# SCH_WINGLET_ADSB.net
KiCad netlist of a schematic drawn in Altium Designer
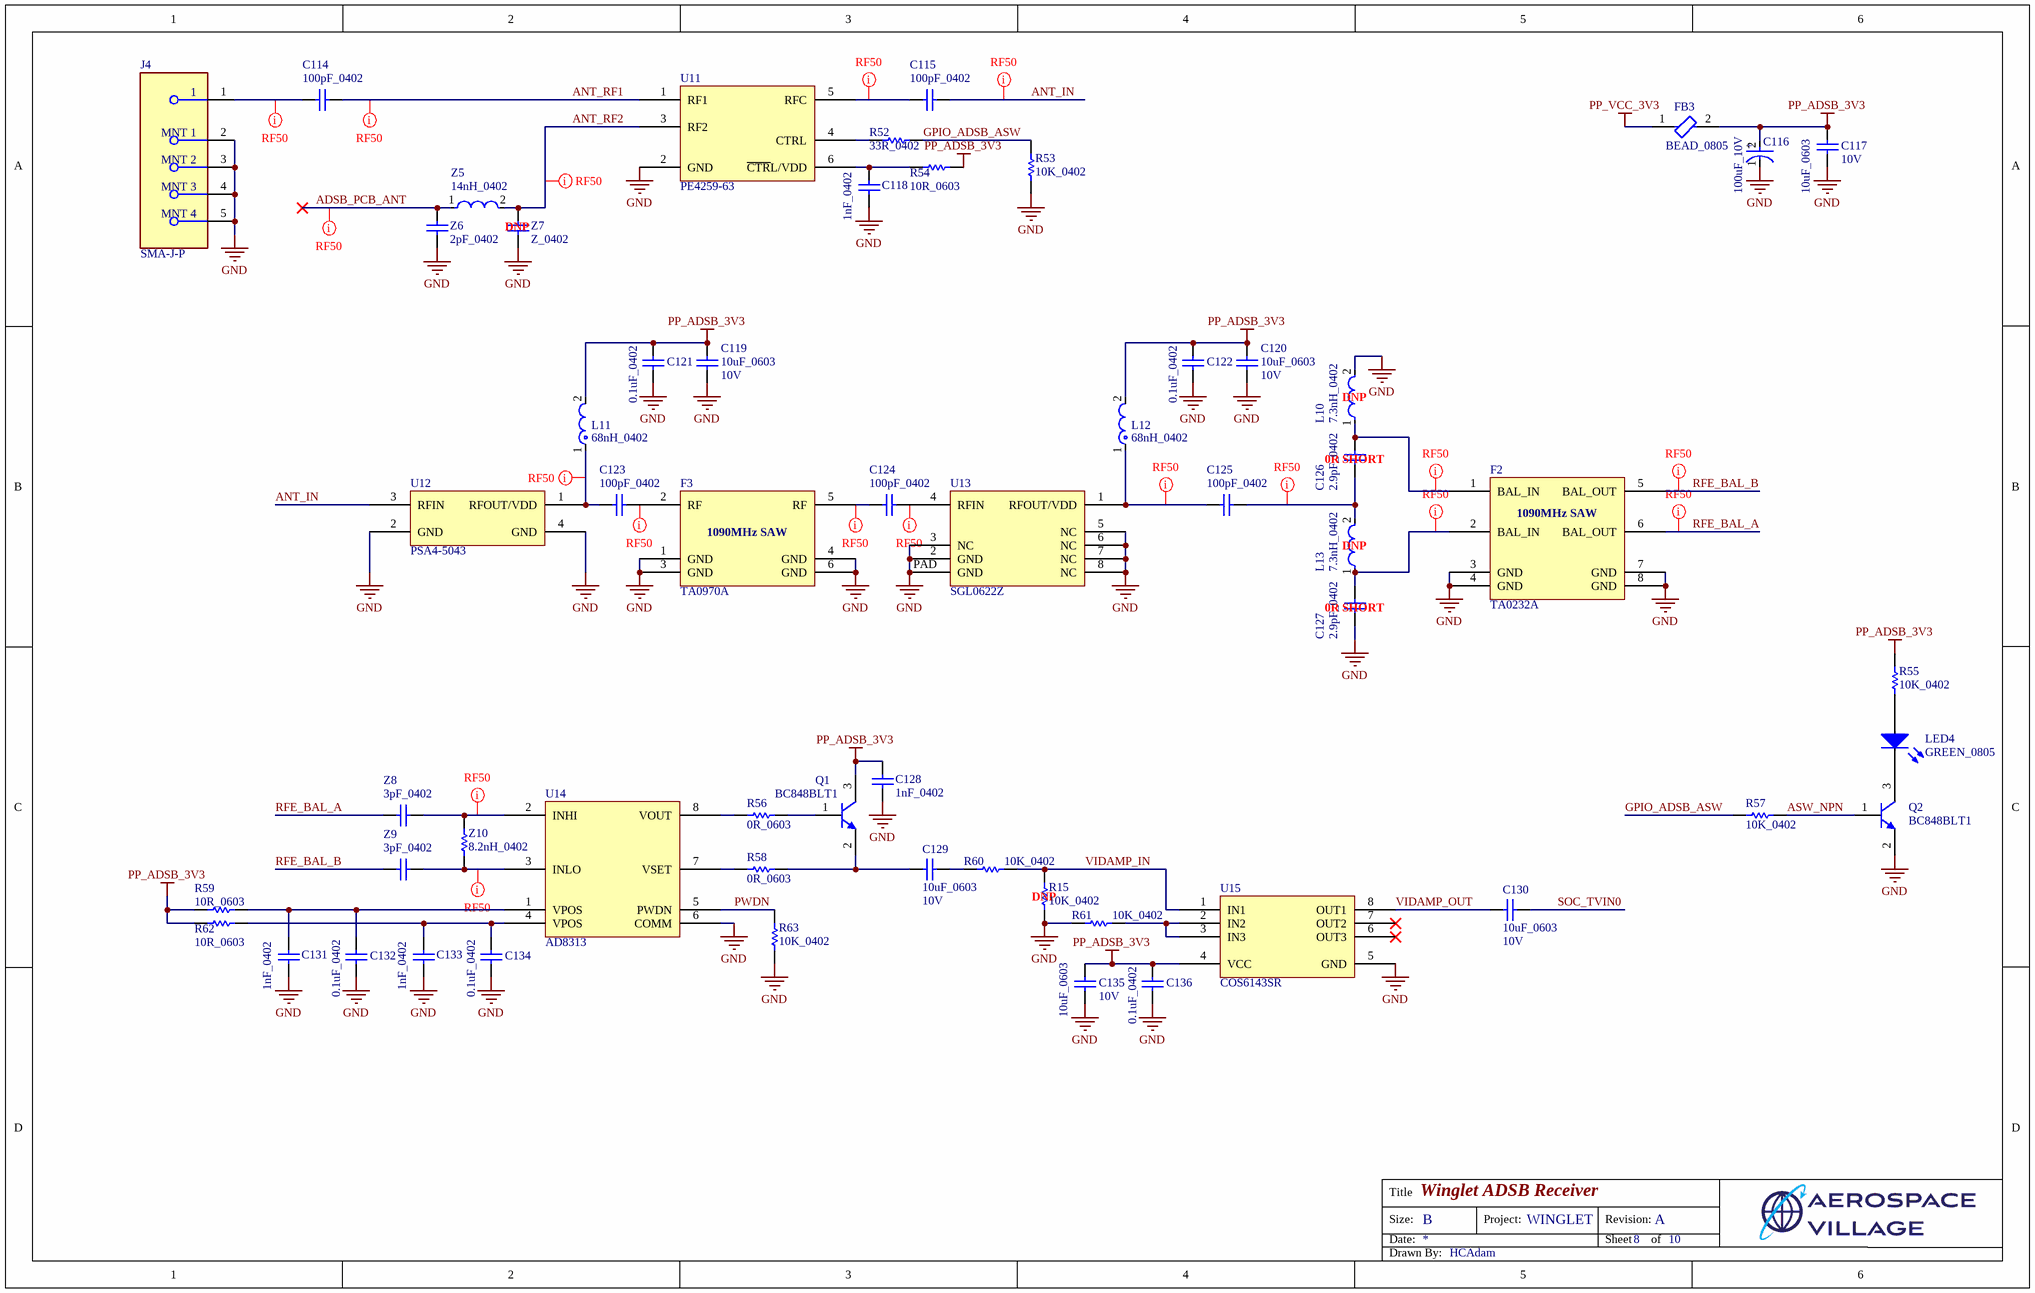
[diagram p0: SCH_WINGLET_ADSB.SchDoc]

(export (version "E")
  (design (tool "Eeschema 10.0.6"))
  (components
    (comp (ref "C114")
      (value "100pF_0402")
      (footprint "CAPC1005X55X25NL05T10")
      (description "GRM1555C1H101JA01D")
      (fields (field (name "MANUFACTURER") "Murata"))
      (libsource (lib "Altium Content Vault") (part "CAP"))
    )
    (comp (ref "C115")
      (value "100pF_0402")
      (footprint "CAPC1005X55X25NL05T10")
      (description "GRM1555C1H101JA01D")
      (fields (field (name "MANUFACTURER") "Murata"))
      (libsource (lib "Altium Content Vault") (part "CAP"))
    )
    (comp (ref "C116")
      (value "100uF_10V")
      (footprint "FP-TAJB-MFG")
      (description "100uF 10V ±10% 1.7Ω SMD CASE-B (3528) Tantalum Capacitor")
      (fields (field (name "VOLTAGE") "6.3V") (field (name "TOLERANCE") "10%"))
      (libsource (lib "Altium Content Vault") (part "203bc49f2ac43e59fd269a8c329ed05"))
    )
    (comp (ref "C117")
      (value "10uF_0603")
      (footprint "CAPC1609X100X15NL20")
      (fields
        (field (name "PART NUMBER") "TACL106M006XTA")
        (field (name "MANUFACTURER") "AVX Interconnect / Elco")
        (field (name "VOLTAGE RATING") "10V")
      )
      (libsource (lib "Altium Content Vault") (part "CAP"))
    )
    (comp (ref "C118")
      (value "1nF_0402")
      (footprint "CAPC1005X56X25NL10T15")
      (description "04025C102KAT4A")
      (fields (field (name "MANUFACTURER") "AVX Interconnect / Elco"))
      (libsource (lib "Altium Content Vault") (part "CAP"))
    )
    (comp (ref "C119")
      (value "10uF_0603")
      (footprint "CAPC1609X100X15NL20")
      (fields
        (field (name "PART NUMBER") "TACL106M006XTA")
        (field (name "MANUFACTURER") "AVX Interconnect / Elco")
        (field (name "VOLTAGE RATING") "10V")
      )
      (libsource (lib "Altium Content Vault") (part "CAP"))
    )
    (comp (ref "C120")
      (value "10uF_0603")
      (footprint "CAPC1609X100X15NL20")
      (fields
        (field (name "PART NUMBER") "TACL106M006XTA")
        (field (name "MANUFACTURER") "AVX Interconnect / Elco")
        (field (name "VOLTAGE RATING") "10V")
      )
      (libsource (lib "Altium Content Vault") (part "CAP"))
    )
    (comp (ref "C121")
      (value "0.1uF_0402")
      (footprint "CAPC1005X56X25NL10T15")
      (description "04026D104KAT2A")
      (fields (field (name "MANUFACTURER") "AVX Interconnect / Elco"))
      (libsource (lib "Altium Content Vault") (part "CAP"))
    )
    (comp (ref "C122")
      (value "0.1uF_0402")
      (footprint "CAPC1005X56X25NL10T15")
      (description "04026D104KAT2A")
      (fields (field (name "MANUFACTURER") "AVX Interconnect / Elco"))
      (libsource (lib "Altium Content Vault") (part "CAP"))
    )
    (comp (ref "C123")
      (value "100pF_0402")
      (footprint "CAPC1005X55X25NL05T10")
      (description "GRM1555C1H101JA01D")
      (fields (field (name "MANUFACTURER") "Murata"))
      (libsource (lib "Altium Content Vault") (part "CAP"))
    )
    (comp (ref "C124")
      (value "100pF_0402")
      (footprint "CAPC1005X55X25NL05T10")
      (description "GRM1555C1H101JA01D")
      (fields (field (name "MANUFACTURER") "Murata"))
      (libsource (lib "Altium Content Vault") (part "CAP"))
    )
    (comp (ref "C125")
      (value "100pF_0402")
      (footprint "CAPC1005X55X25NL05T10")
      (description "GRM1555C1H101JA01D")
      (fields (field (name "MANUFACTURER") "Murata"))
      (libsource (lib "Altium Content Vault") (part "CAP"))
    )
    (comp (ref "C126")
      (value "2.9pF_0402")
      (footprint "CAPC1006X50X20NL10T10")
      (description "04023J2R9BBSTR")
      (fields (field (name "MANUFACTURER") "AVX Interconnect / Elco") (field (name "0R SHORT") "0R SHORT"))
      (libsource (lib "Altium Content Vault") (part "CAP"))
    )
    (comp (ref "C127")
      (value "2.9pF_0402")
      (footprint "CAPC1006X50X20NL10T10")
      (description "04023J2R9BBSTR")
      (fields (field (name "MANUFACTURER") "AVX Interconnect / Elco") (field (name "0R SHORT") "0R SHORT"))
      (libsource (lib "Altium Content Vault") (part "CAP"))
    )
    (comp (ref "C128")
      (value "1nF_0402")
      (footprint "CAPC1005X56X25NL10T15")
      (description "04025C102KAT4A")
      (fields (field (name "MANUFACTURER") "AVX Interconnect / Elco"))
      (libsource (lib "Altium Content Vault") (part "CAP"))
    )
    (comp (ref "C129")
      (value "10uF_0603")
      (footprint "CAPC1609X100X15NL20")
      (fields
        (field (name "PART NUMBER") "TACL106M006XTA")
        (field (name "MANUFACTURER") "AVX Interconnect / Elco")
        (field (name "VOLTAGE RATING") "10V")
      )
      (libsource (lib "Altium Content Vault") (part "CAP"))
    )
    (comp (ref "C130")
      (value "10uF_0603")
      (footprint "CAPC1609X100X15NL20")
      (fields
        (field (name "PART NUMBER") "TACL106M006XTA")
        (field (name "MANUFACTURER") "AVX Interconnect / Elco")
        (field (name "VOLTAGE RATING") "10V")
      )
      (libsource (lib "Altium Content Vault") (part "CAP"))
    )
    (comp (ref "C131")
      (value "1nF_0402")
      (footprint "CAPC1005X56X25NL10T15")
      (description "04025C102KAT4A")
      (fields (field (name "MANUFACTURER") "AVX Interconnect / Elco"))
      (libsource (lib "Altium Content Vault") (part "CAP"))
    )
    (comp (ref "C132")
      (value "0.1uF_0402")
      (footprint "CAPC1005X56X25NL10T15")
      (description "04026D104KAT2A")
      (fields (field (name "MANUFACTURER") "AVX Interconnect / Elco"))
      (libsource (lib "Altium Content Vault") (part "CAP"))
    )
    (comp (ref "C133")
      (value "1nF_0402")
      (footprint "CAPC1005X56X25NL10T15")
      (description "04025C102KAT4A")
      (fields (field (name "MANUFACTURER") "AVX Interconnect / Elco"))
      (libsource (lib "Altium Content Vault") (part "CAP"))
    )
    (comp (ref "C134")
      (value "0.1uF_0402")
      (footprint "CAPC1005X56X25NL10T15")
      (description "04026D104KAT2A")
      (fields (field (name "MANUFACTURER") "AVX Interconnect / Elco"))
      (libsource (lib "Altium Content Vault") (part "CAP"))
    )
    (comp (ref "C135")
      (value "10uF_0603")
      (footprint "CAPC1609X100X15NL20")
      (fields
        (field (name "PART NUMBER") "TACL106M006XTA")
        (field (name "MANUFACTURER") "AVX Interconnect / Elco")
        (field (name "VOLTAGE RATING") "10V")
      )
      (libsource (lib "Altium Content Vault") (part "CAP"))
    )
    (comp (ref "C136")
      (value "0.1uF_0402")
      (footprint "CAPC1005X56X25NL10T15")
      (description "04026D104KAT2A")
      (fields (field (name "MANUFACTURER") "AVX Interconnect / Elco"))
      (libsource (lib "Altium Content Vault") (part "CAP"))
    )
    (comp (ref "F2")
      (value "TA0232A")
      (footprint "LCCS127P380X380X125-8N")
      (description "SAW Filter 1090MHz Balanced SMD 3.8x3.8mm")
      (libsource (lib "DCAV32_WINGLET_SCHLIB") (part "TA0232A"))
    )
    (comp (ref "F3")
      (value "TA0970A")
      (footprint "LCCS127P380X380X125-6N")
      (description "SAW Filter 1090MHz Unbalanced SMD 3.8x3.8mm")
      (libsource (lib "DCAV32_WINGLET_SCHLIB") (part "TA0970A"))
    )
    (comp (ref "FB3")
      (value "BEAD_0805")
      (footprint "FP-BLM21-0_2-t0_85-e0_5-IPC_B")
      (description "Chip Ferrite Bead, 0805, 150Ω @ 100MHz, 0.09Ω, 25%, 1A")
      (fields (field (name "TOLERANCE") "25%"))
      (libsource (lib "Altium Content Vault") (part "5f30dd21d616792df468990f7003faa"))
    )
    (comp (ref "J4")
      (value "SMA-J-P")
      (footprint "FP-SMA-J-P-H-ST-EM1-MFG")
      (description "CONN SMA JACK STR 50OHM EDGE MNT\r\nSMA-J-P-H-ST-EM1")
      (libsource (lib "Altium Content Vault") (part "c65b8a639cdaef1819ea20b5466f8fa"))
    )
    (comp (ref "L10")
      (value "7.3nH_0402")
      (footprint "FP-LQW15AN_00-W0_6-0_1-MFG")
      (description "Wire Wound RF Inductor 7.3nH ±3% 570mA 0.13Ω 0402 (1005)\r\nLQW15AN7N3H00D")
      (fields (field (name "TOLERANCE") "3%") (field (name "DNP") "DNP"))
      (libsource (lib "Altium Content Vault") (part "725321dda6339637d4d059423bc1c3c"))
    )
    (comp (ref "L11")
      (value "68nH_0402")
      (footprint "FP-LQG15HH_02-MFG")
      (description "Multilayer type RF Inductor 68nH ±5% 0.92Ω 250mA 0402\r\nLQG15HS68NJ02D")
      (fields (field (name "TOLERANCE") "5%"))
      (libsource (lib "Altium Content Vault") (part "4cc4b267dca4c8e51f7102f422741d8"))
    )
    (comp (ref "L12")
      (value "68nH_0402")
      (footprint "FP-LQG15HH_02-MFG")
      (description "Multilayer type RF Inductor 68nH ±5% 0.92Ω 250mA 0402\r\nLQG15HS68NJ02D")
      (fields (field (name "TOLERANCE") "5%"))
      (libsource (lib "Altium Content Vault") (part "4cc4b267dca4c8e51f7102f422741d8"))
    )
    (comp (ref "L13")
      (value "7.3nH_0402")
      (footprint "FP-LQW15AN_00-W0_6-0_1-MFG")
      (description "Wire Wound RF Inductor 7.3nH ±3% 570mA 0.13Ω 0402 (1005)\r\nLQW15AN7N3H00D")
      (fields (field (name "TOLERANCE") "3%") (field (name "DNP") "DNP"))
      (libsource (lib "Altium Content Vault") (part "725321dda6339637d4d059423bc1c3c"))
    )
    (comp (ref "LED4")
      (value "GREEN_0805")
      (footprint "0805_A")
      (description "SMD mono-color Chip LED, WL-SMCW, Green\r\n150080GS75000")
      (fields (field (name "PARTNUMBER") "150080GS75000") (field (name "MANUFACTURER") "Wuerth Elektronik"))
      (libsource (lib "Altium Content Vault") (part "WE-LED_K1A2-2"))
    )
    (comp (ref "Q1")
      (value "BC848BLT1")
      (footprint "ONSC-SOT-23-3-318-08_V")
      (description "General Purpose Transistor, NPN Silicon, 3-Pin SOT-23, Tape and Reel")
      (fields (field (name "MANUFACTURER") "On Semiconductor"))
      (libsource (lib "Altium Content Vault") (part "ONSC-NPN-B1E2C3-3"))
    )
    (comp (ref "Q2")
      (value "BC848BLT1")
      (footprint "ONSC-SOT-23-3-318-08_V")
      (description "General Purpose Transistor, NPN Silicon, 3-Pin SOT-23, Tape and Reel")
      (fields (field (name "MANUFACTURER") "On Semiconductor"))
      (libsource (lib "Altium Content Vault") (part "ONSC-NPN-B1E2C3-3"))
    )
    (comp (ref "R15")
      (value "10K_0402")
      (footprint "RESC1005X40X25NL05T05")
      (fields
        (field (name "TOLERANCE") "1%")
        (field (name "MANUFACTURER") "Panasonic")
        (field (name "DNP") "DNP")
      )
      (libsource (lib "Altium Content Vault") (part "RES-2"))
    )
    (comp (ref "R52")
      (value "33R_0402")
      (footprint "RESC1005X40X25NL05T05")
      (description "ERJ2RKF33R0X")
      (fields (field (name "MANUFACTURER") "Panasonic"))
      (libsource (lib "Altium Content Vault") (part "RES"))
    )
    (comp (ref "R53")
      (value "10K_0402")
      (footprint "RESC1005X40X25NL05T05")
      (fields (field (name "TOLERANCE") "1%") (field (name "MANUFACTURER") "Panasonic"))
      (libsource (lib "Altium Content Vault") (part "RES-2"))
    )
    (comp (ref "R54")
      (value "10R_0603")
      (footprint "RESC1608X55X25NL10T15")
      (fields (field (name "MANUFACTURER") "Yageo"))
      (libsource (lib "Altium Content Vault") (part "RES-2"))
    )
    (comp (ref "R55")
      (value "10K_0402")
      (footprint "RESC1005X40X25NL05T05")
      (fields (field (name "TOLERANCE") "1%") (field (name "MANUFACTURER") "Panasonic"))
      (libsource (lib "Altium Content Vault") (part "RES-2"))
    )
    (comp (ref "R56")
      (value "0R_0603")
      (footprint "RESC1608X55X25LL10T15")
      (description "RC0603JR-100RL")
      (fields (field (name "MANUFACTURER") "Yageo"))
      (libsource (lib "Altium Content Vault") (part "RES"))
    )
    (comp (ref "R57")
      (value "10K_0402")
      (footprint "RESC1005X40X25NL05T05")
      (fields (field (name "TOLERANCE") "1%") (field (name "MANUFACTURER") "Panasonic"))
      (libsource (lib "Altium Content Vault") (part "RES-2"))
    )
    (comp (ref "R58")
      (value "0R_0603")
      (footprint "RESC1608X55X25LL10T15")
      (description "RC0603JR-100RL")
      (fields (field (name "MANUFACTURER") "Yageo"))
      (libsource (lib "Altium Content Vault") (part "RES"))
    )
    (comp (ref "R59")
      (value "10R_0603")
      (footprint "RESC1608X55X25NL10T15")
      (fields (field (name "MANUFACTURER") "Yageo"))
      (libsource (lib "Altium Content Vault") (part "RES-2"))
    )
    (comp (ref "R60")
      (value "10K_0402")
      (footprint "RESC1005X40X25NL05T05")
      (fields (field (name "TOLERANCE") "1%") (field (name "MANUFACTURER") "Panasonic"))
      (libsource (lib "Altium Content Vault") (part "RES-2"))
    )
    (comp (ref "R61")
      (value "10K_0402")
      (footprint "RESC1005X40X25NL05T05")
      (fields (field (name "TOLERANCE") "1%") (field (name "MANUFACTURER") "Panasonic"))
      (libsource (lib "Altium Content Vault") (part "RES-2"))
    )
    (comp (ref "R62")
      (value "10R_0603")
      (footprint "RESC1608X55X25NL10T15")
      (fields (field (name "MANUFACTURER") "Yageo"))
      (libsource (lib "Altium Content Vault") (part "RES-2"))
    )
    (comp (ref "R63")
      (value "10K_0402")
      (footprint "RESC1005X40X25NL05T05")
      (fields (field (name "TOLERANCE") "1%") (field (name "MANUFACTURER") "Panasonic"))
      (libsource (lib "Altium Content Vault") (part "RES-2"))
    )
    (comp (ref "U11")
      (value "PE4259-63")
      (footprint "SOT65P210X100-6N")
      (description "SPDT High Power UltraCMOS®  \r\n10 MHz–3.0 GHz RF Switch")
      (libsource (lib "DCAV32_WINGLET_SCHLIB") (part "PE4259"))
    )
    (comp (ref "U12")
      (value "PSA4-5043")
      (footprint "SOT343P210X110-4N-MMM")
      (description "50Ω 0.05 to 4 GHz Ultra-Low Noise MMIC Amplifier")
      (libsource (lib "DCAV32_WINGLET_SCHLIB") (part "PSA4-5043"))
    )
    (comp (ref "U13")
      (value "SGL0622Z")
      (footprint "SON50P200X90_HS-9N")
      (description "5 MHz to 4000 MHz, Low-Noise SiGe HBT MMIC Amplifier")
      (libsource (lib "DCAV32_WINGLET_SCHLIB") (part "SGL0622Z"))
    )
    (comp (ref "U14")
      (value "AD8313")
      (footprint "TSOP65P490X110-8N-AD8313")
      (description "0.1 GHz to 2.5 GHz 70 dB Logarithmic Detector/Controller")
      (libsource (lib "DCAV32_WINGLET_SCHLIB") (part "AD8313"))
    )
    (comp (ref "U15")
      (value "COS6143SR")
      (footprint "SOP127P600X175-8N")
      (description "Triple, 6th Order, Standard Definition Video Filter Driver")
      (libsource (lib "DCAV32_WINGLET_SCHLIB") (part "COS6143SR"))
    )
    (comp (ref "Z5")
      (value "14nH_0402")
      (footprint "FP-LQW15AN_80-MFG")
      (description "Wire Wound RF Inductor 14nH ±2% 1150mA 0.111Ω 0402 (1005)\r\nLQW15AN14NG80D")
      (fields (field (name "TOLERANCE") "2%"))
      (libsource (lib "Altium Content Vault") (part "725321dda6339637d4d059423bc1c3c"))
    )
    (comp (ref "Z6")
      (value "2pF_0402")
      (footprint "CAPC1005X55X25NL05T10")
      (description "GRM1555C1H2R0CA01D")
      (fields (field (name "MANUFACTURER") "Murata"))
      (libsource (lib "Altium Content Vault") (part "CAP"))
    )
    (comp (ref "Z7")
      (value "Z_0402")
      (footprint "CAPC1005X55X25NL05T10")
      (description "GRM1555C1H2R0CA01D")
      (fields (field (name "MANUFACTURER") "Murata") (field (name "DNP") "DNP"))
      (libsource (lib "Altium Content Vault") (part "CAP"))
    )
    (comp (ref "Z8")
      (value "3pF_0402")
      (footprint "CAPC1006X50X20NL10T10")
      (fields
        (field (name "MANUFACTURER") "AVX Interconnect / Elco")
        (field (name "PART NUMBER") "0402YJ100FBSTR")
      )
      (libsource (lib "Altium Content Vault") (part "CAP"))
    )
    (comp (ref "Z9")
      (value "3pF_0402")
      (footprint "CAPC1006X50X20NL10T10")
      (fields
        (field (name "MANUFACTURER") "AVX Interconnect / Elco")
        (field (name "PART NUMBER") "0402YJ100FBSTR")
      )
      (libsource (lib "Altium Content Vault") (part "CAP"))
    )
    (comp (ref "Z10")
      (value "8.2nH_0402")
      (footprint "RESC1005X40X25NL05T05")
      (fields (field (name "TOLERANCE") "1%") (field (name "MANUFACTURER") "Panasonic"))
      (libsource (lib "Altium Content Vault") (part "RES-2"))
    )
  )
  (nets
    (net (code "1") (name "/ADSB_PCB_ANT") (class "Default")
      (node (ref "Z5") (pin "1") (pinfunction "1_1") (pintype "passive"))
      (node (ref "Z6") (pin "2") (pinfunction "2_2") (pintype "passive"))
    )
    (net (code "2") (name "/ANT_IN") (class "Default")
      (node (ref "C115") (pin "2") (pinfunction "2_2") (pintype "passive"))
      (node (ref "U12") (pin "3") (pinfunction "RFIN_3") (pintype "passive"))
    )
    (net (code "3") (name "/ANT_RF1") (class "Default")
      (node (ref "C114") (pin "2") (pinfunction "2_2") (pintype "passive"))
      (node (ref "U11") (pin "1") (pinfunction "RF1_1") (pintype "passive"))
    )
    (net (code "4") (name "/ANT_RF2") (class "Default")
      (node (ref "U11") (pin "3") (pinfunction "RF2_3") (pintype "passive"))
      (node (ref "Z5") (pin "2") (pinfunction "2_2") (pintype "passive"))
      (node (ref "Z7") (pin "2") (pinfunction "2_2") (pintype "passive"))
    )
    (net (code "5") (name "/ASW_NPN") (class "Default")
      (node (ref "Q2") (pin "1") (pinfunction "B_1") (pintype "passive"))
      (node (ref "R57") (pin "1") (pinfunction "1_1") (pintype "passive"))
    )
    (net (code "6") (name "/GPIO_ADSB_ASW") (class "Default")
      (node (ref "R52") (pin "2") (pinfunction "2_2") (pintype "passive"))
      (node (ref "R53") (pin "2") (pinfunction "2_2") (pintype "passive"))
      (node (ref "R57") (pin "2") (pinfunction "2_2") (pintype "passive"))
    )
    (net (code "7") (name "/PWDN") (class "Default")
      (node (ref "R63") (pin "2") (pinfunction "2_2") (pintype "passive"))
      (node (ref "U14") (pin "5") (pinfunction "PWDN_5") (pintype "passive"))
    )
    (net (code "8") (name "/RFE_BAL_A") (class "Default")
      (node (ref "F2") (pin "6") (pinfunction "BAL_OUT_6") (pintype "passive"))
      (node (ref "Z8") (pin "2") (pinfunction "2_2") (pintype "passive"))
    )
    (net (code "9") (name "/RFE_BAL_B") (class "Default")
      (node (ref "F2") (pin "5") (pinfunction "BAL_OUT_5") (pintype "passive"))
      (node (ref "Z9") (pin "2") (pinfunction "2_2") (pintype "passive"))
    )
    (net (code "10") (name "/SOC_TVIN0") (class "Default")
      (node (ref "C130") (pin "1") (pinfunction "1_1") (pintype "passive"))
    )
    (net (code "11") (name "/VIDAMP_IN") (class "Default")
      (node (ref "R15") (pin "2") (pinfunction "2_2") (pintype "passive"))
      (node (ref "R60") (pin "2") (pinfunction "2_2") (pintype "passive"))
      (node (ref "U15") (pin "1") (pinfunction "IN1_1") (pintype "passive"))
    )
    (net (code "12") (name "/VIDAMP_OUT") (class "Default")
      (node (ref "C130") (pin "2") (pinfunction "2_2") (pintype "passive"))
      (node (ref "U15") (pin "8") (pinfunction "OUT1_8") (pintype "passive"))
    )
    (net (code "13") (name "GND") (class "Default")
      (node (ref "C116") (pin "1") (pinfunction "C_1") (pintype "passive"))
      (node (ref "C117") (pin "1") (pinfunction "1_1") (pintype "passive"))
      (node (ref "C118") (pin "1") (pinfunction "1_1") (pintype "passive"))
      (node (ref "C119") (pin "1") (pinfunction "1_1") (pintype "passive"))
      (node (ref "C120") (pin "1") (pinfunction "1_1") (pintype "passive"))
      (node (ref "C121") (pin "1") (pinfunction "1_1") (pintype "passive"))
      (node (ref "C122") (pin "1") (pinfunction "1_1") (pintype "passive"))
      (node (ref "C127") (pin "1") (pinfunction "1_1") (pintype "passive"))
      (node (ref "C128") (pin "1") (pinfunction "1_1") (pintype "passive"))
      (node (ref "C131") (pin "1") (pinfunction "1_1") (pintype "passive"))
      (node (ref "C132") (pin "1") (pinfunction "1_1") (pintype "passive"))
      (node (ref "C133") (pin "1") (pinfunction "1_1") (pintype "passive"))
      (node (ref "C134") (pin "1") (pinfunction "1_1") (pintype "passive"))
      (node (ref "C135") (pin "1") (pinfunction "1_1") (pintype "passive"))
      (node (ref "C136") (pin "1") (pinfunction "1_1") (pintype "passive"))
      (node (ref "F2") (pin "3") (pinfunction "GND_3") (pintype "passive"))
      (node (ref "F2") (pin "4") (pinfunction "GND_4") (pintype "passive"))
      (node (ref "F2") (pin "7") (pinfunction "GND_7") (pintype "passive"))
      (node (ref "F2") (pin "8") (pinfunction "GND_8") (pintype "passive"))
      (node (ref "F3") (pin "1") (pinfunction "GND_1") (pintype "passive"))
      (node (ref "F3") (pin "3") (pinfunction "GND_3") (pintype "passive"))
      (node (ref "F3") (pin "4") (pinfunction "GND_4") (pintype "passive"))
      (node (ref "F3") (pin "6") (pinfunction "GND_6") (pintype "passive"))
      (node (ref "J4") (pin "2") (pinfunction "MNT_1_2") (pintype "passive"))
      (node (ref "J4") (pin "3") (pinfunction "MNT_2_3") (pintype "passive"))
      (node (ref "J4") (pin "4") (pinfunction "MNT_3_4") (pintype "passive"))
      (node (ref "J4") (pin "5") (pinfunction "MNT_4_5") (pintype "passive"))
      (node (ref "L10") (pin "2") (pinfunction "2_2") (pintype "passive"))
      (node (ref "Q2") (pin "2") (pinfunction "E_2") (pintype "passive"))
      (node (ref "R15") (pin "1") (pinfunction "1_1") (pintype "passive"))
      (node (ref "R53") (pin "1") (pinfunction "1_1") (pintype "passive"))
      (node (ref "R61") (pin "1") (pinfunction "1_1") (pintype "passive"))
      (node (ref "R63") (pin "1") (pinfunction "1_1") (pintype "passive"))
      (node (ref "U11") (pin "2") (pinfunction "GND_2") (pintype "passive"))
      (node (ref "U12") (pin "2") (pinfunction "GND_2") (pintype "passive"))
      (node (ref "U12") (pin "4") (pinfunction "GND_4") (pintype "passive"))
      (node (ref "U13") (pin "2") (pinfunction "GND_2") (pintype "passive"))
      (node (ref "U13") (pin "3") (pinfunction "NC_3") (pintype "passive"))
      (node (ref "U13") (pin "5") (pinfunction "NC_5") (pintype "passive"))
      (node (ref "U13") (pin "6") (pinfunction "NC_6") (pintype "passive"))
      (node (ref "U13") (pin "7") (pinfunction "NC_7") (pintype "passive"))
      (node (ref "U13") (pin "8") (pinfunction "NC_8") (pintype "passive"))
      (node (ref "U13") (pin "PAD") (pinfunction "GND_PAD") (pintype "passive"))
      (node (ref "U14") (pin "6") (pinfunction "COMM_6") (pintype "passive"))
      (node (ref "U15") (pin "5") (pinfunction "GND_5") (pintype "passive"))
      (node (ref "Z6") (pin "1") (pinfunction "1_1") (pintype "passive"))
      (node (ref "Z7") (pin "1") (pinfunction "1_1") (pintype "passive"))
    )
    (net (code "14") (name "Net-(C114-Pad1)") (class "Default")
      (node (ref "C114") (pin "1") (pinfunction "1_1") (pintype "passive"))
      (node (ref "J4") (pin "1") (pinfunction "1_1") (pintype "passive"))
    )
    (net (code "15") (name "Net-(C123-Pad2)") (class "Default")
      (node (ref "C123") (pin "2") (pinfunction "2_2") (pintype "passive"))
      (node (ref "F3") (pin "2") (pinfunction "RF_2") (pintype "passive"))
    )
    (net (code "16") (name "Net-(C124-Pad1)") (class "Default")
      (node (ref "C124") (pin "1") (pinfunction "1_1") (pintype "passive"))
      (node (ref "F3") (pin "5") (pinfunction "RF_5") (pintype "passive"))
    )
    (net (code "17") (name "Net-(C125-Pad2)") (class "Default")
      (node (ref "C125") (pin "2") (pinfunction "2_2") (pintype "passive"))
      (node (ref "C126") (pin "1") (pinfunction "1_1") (pintype "passive"))
      (node (ref "L13") (pin "2") (pinfunction "2_2") (pintype "passive"))
    )
    (net (code "18") (name "Net-(C126-Pad2)") (class "Default")
      (node (ref "C126") (pin "2") (pinfunction "2_2") (pintype "passive"))
      (node (ref "F2") (pin "1") (pinfunction "BAL_IN_1") (pintype "passive"))
      (node (ref "L10") (pin "1") (pinfunction "1_1") (pintype "passive"))
    )
    (net (code "19") (name "Net-(C127-Pad2)") (class "Default")
      (node (ref "C127") (pin "2") (pinfunction "2_2") (pintype "passive"))
      (node (ref "F2") (pin "2") (pinfunction "BAL_IN_2") (pintype "passive"))
      (node (ref "L13") (pin "1") (pinfunction "1_1") (pintype "passive"))
    )
    (net (code "20") (name "Net-(C129-Pad1)") (class "Default")
      (node (ref "C129") (pin "1") (pinfunction "1_1") (pintype "passive"))
      (node (ref "R60") (pin "1") (pinfunction "1_1") (pintype "passive"))
    )
    (net (code "21") (name "Net-(C131-Pad2)") (class "Default")
      (node (ref "C131") (pin "2") (pinfunction "2_2") (pintype "passive"))
      (node (ref "C132") (pin "2") (pinfunction "2_2") (pintype "passive"))
      (node (ref "R59") (pin "2") (pinfunction "2_2") (pintype "passive"))
      (node (ref "U14") (pin "1") (pinfunction "VPOS_1") (pintype "passive"))
    )
    (net (code "22") (name "Net-(C133-Pad2)") (class "Default")
      (node (ref "C133") (pin "2") (pinfunction "2_2") (pintype "passive"))
      (node (ref "C134") (pin "2") (pinfunction "2_2") (pintype "passive"))
      (node (ref "R62") (pin "2") (pinfunction "2_2") (pintype "passive"))
      (node (ref "U14") (pin "4") (pinfunction "VPOS_4") (pintype "passive"))
    )
    (net (code "23") (name "Net-(LED4-A)") (class "Default")
      (node (ref "LED4") (pin "2") (pinfunction "A_2") (pintype "passive"))
      (node (ref "R55") (pin "1") (pinfunction "1_1") (pintype "passive"))
    )
    (net (code "24") (name "Net-(LED4-K)") (class "Default")
      (node (ref "LED4") (pin "1") (pinfunction "K_1") (pintype "passive"))
      (node (ref "Q2") (pin "3") (pinfunction "C_3") (pintype "passive"))
    )
    (net (code "25") (name "Net-(Q1-B)") (class "Default")
      (node (ref "Q1") (pin "1") (pinfunction "B_1") (pintype "passive"))
      (node (ref "R56") (pin "1") (pinfunction "1_1") (pintype "passive"))
    )
    (net (code "26") (name "Net-(Q1-E)") (class "Default")
      (node (ref "C129") (pin "2") (pinfunction "2_2") (pintype "passive"))
      (node (ref "Q1") (pin "2") (pinfunction "E_2") (pintype "passive"))
      (node (ref "R58") (pin "1") (pinfunction "1_1") (pintype "passive"))
    )
    (net (code "27") (name "Net-(U11-CTRL)") (class "Default")
      (node (ref "R52") (pin "1") (pinfunction "1_1") (pintype "passive"))
      (node (ref "U11") (pin "4") (pinfunction "CTRL_4") (pintype "passive"))
    )
    (net (code "28") (name "Net-(U11-RFC)") (class "Default")
      (node (ref "C115") (pin "1") (pinfunction "1_1") (pintype "passive"))
      (node (ref "U11") (pin "5") (pinfunction "RFC_5") (pintype "passive"))
    )
    (net (code "29") (name "Net-(U11-~{CTR}L{slash}VDD)") (class "Default")
      (node (ref "C118") (pin "2") (pinfunction "2_2") (pintype "passive"))
      (node (ref "R54") (pin "1") (pinfunction "1_1") (pintype "passive"))
      (node (ref "U11") (pin "6") (pinfunction "~{CTR}L/VDD_6") (pintype "passive"))
    )
    (net (code "30") (name "Net-(U12-RFOUT{slash}VDD)") (class "Default")
      (node (ref "C123") (pin "1") (pinfunction "1_1") (pintype "passive"))
      (node (ref "L11") (pin "1") (pinfunction "1_1") (pintype "passive"))
      (node (ref "U12") (pin "1") (pinfunction "RFOUT/VDD_1") (pintype "passive"))
    )
    (net (code "31") (name "Net-(U13-RFIN)") (class "Default")
      (node (ref "C124") (pin "2") (pinfunction "2_2") (pintype "passive"))
      (node (ref "U13") (pin "4") (pinfunction "RFIN_4") (pintype "passive"))
    )
    (net (code "32") (name "Net-(U13-RFOUT{slash}VDD)") (class "Default")
      (node (ref "C125") (pin "1") (pinfunction "1_1") (pintype "passive"))
      (node (ref "L12") (pin "1") (pinfunction "1_1") (pintype "passive"))
      (node (ref "U13") (pin "1") (pinfunction "RFOUT/VDD_1") (pintype "passive"))
    )
    (net (code "33") (name "Net-(U14-INHI)") (class "Default")
      (node (ref "U14") (pin "2") (pinfunction "INHI_2") (pintype "passive"))
      (node (ref "Z10") (pin "2") (pinfunction "2_2") (pintype "passive"))
      (node (ref "Z8") (pin "1") (pinfunction "1_1") (pintype "passive"))
    )
    (net (code "34") (name "Net-(U14-INLO)") (class "Default")
      (node (ref "U14") (pin "3") (pinfunction "INLO_3") (pintype "passive"))
      (node (ref "Z10") (pin "1") (pinfunction "1_1") (pintype "passive"))
      (node (ref "Z9") (pin "1") (pinfunction "1_1") (pintype "passive"))
    )
    (net (code "35") (name "Net-(U14-VOUT)") (class "Default")
      (node (ref "R56") (pin "2") (pinfunction "2_2") (pintype "passive"))
      (node (ref "U14") (pin "8") (pinfunction "VOUT_8") (pintype "passive"))
    )
    (net (code "36") (name "Net-(U14-VSET)") (class "Default")
      (node (ref "R58") (pin "2") (pinfunction "2_2") (pintype "passive"))
      (node (ref "U14") (pin "7") (pinfunction "VSET_7") (pintype "passive"))
    )
    (net (code "37") (name "Net-(U15-IN2)") (class "Default")
      (node (ref "R61") (pin "2") (pinfunction "2_2") (pintype "passive"))
      (node (ref "U15") (pin "2") (pinfunction "IN2_2") (pintype "passive"))
      (node (ref "U15") (pin "3") (pinfunction "IN3_3") (pintype "passive"))
    )
    (net (code "38") (name "PP_ADSB_3V3") (class "Default")
      (node (ref "C116") (pin "2") (pinfunction "A_2") (pintype "passive"))
      (node (ref "C117") (pin "2") (pinfunction "2_2") (pintype "passive"))
      (node (ref "C119") (pin "2") (pinfunction "2_2") (pintype "passive"))
      (node (ref "C120") (pin "2") (pinfunction "2_2") (pintype "passive"))
      (node (ref "C121") (pin "2") (pinfunction "2_2") (pintype "passive"))
      (node (ref "C122") (pin "2") (pinfunction "2_2") (pintype "passive"))
      (node (ref "C128") (pin "2") (pinfunction "2_2") (pintype "passive"))
      (node (ref "C135") (pin "2") (pinfunction "2_2") (pintype "passive"))
      (node (ref "C136") (pin "2") (pinfunction "2_2") (pintype "passive"))
      (node (ref "FB3") (pin "2") (pinfunction "2_2") (pintype "passive"))
      (node (ref "L11") (pin "2") (pinfunction "2_2") (pintype "passive"))
      (node (ref "L12") (pin "2") (pinfunction "2_2") (pintype "passive"))
      (node (ref "Q1") (pin "3") (pinfunction "C_3") (pintype "passive"))
      (node (ref "R54") (pin "2") (pinfunction "2_2") (pintype "passive"))
      (node (ref "R55") (pin "2") (pinfunction "2_2") (pintype "passive"))
      (node (ref "R59") (pin "1") (pinfunction "1_1") (pintype "passive"))
      (node (ref "R62") (pin "1") (pinfunction "1_1") (pintype "passive"))
      (node (ref "U15") (pin "4") (pinfunction "VCC_4") (pintype "passive"))
    )
    (net (code "39") (name "PP_VCC_3V3") (class "Default")
      (node (ref "FB3") (pin "1") (pinfunction "1_1") (pintype "passive"))
    )
    (net (code "40") (name "unconnected-(U15-OUT2-Pad7)") (class "Default")
      (node (ref "U15") (pin "7") (pinfunction "OUT2_7") (pintype "passive+no_connect"))
    )
    (net (code "41") (name "unconnected-(U15-OUT3-Pad6)") (class "Default")
      (node (ref "U15") (pin "6") (pinfunction "OUT3_6") (pintype "passive+no_connect"))
    )
  )
)
